# 2_ALARM.net
KiCad netlist of a schematic drawn in Altium Designer
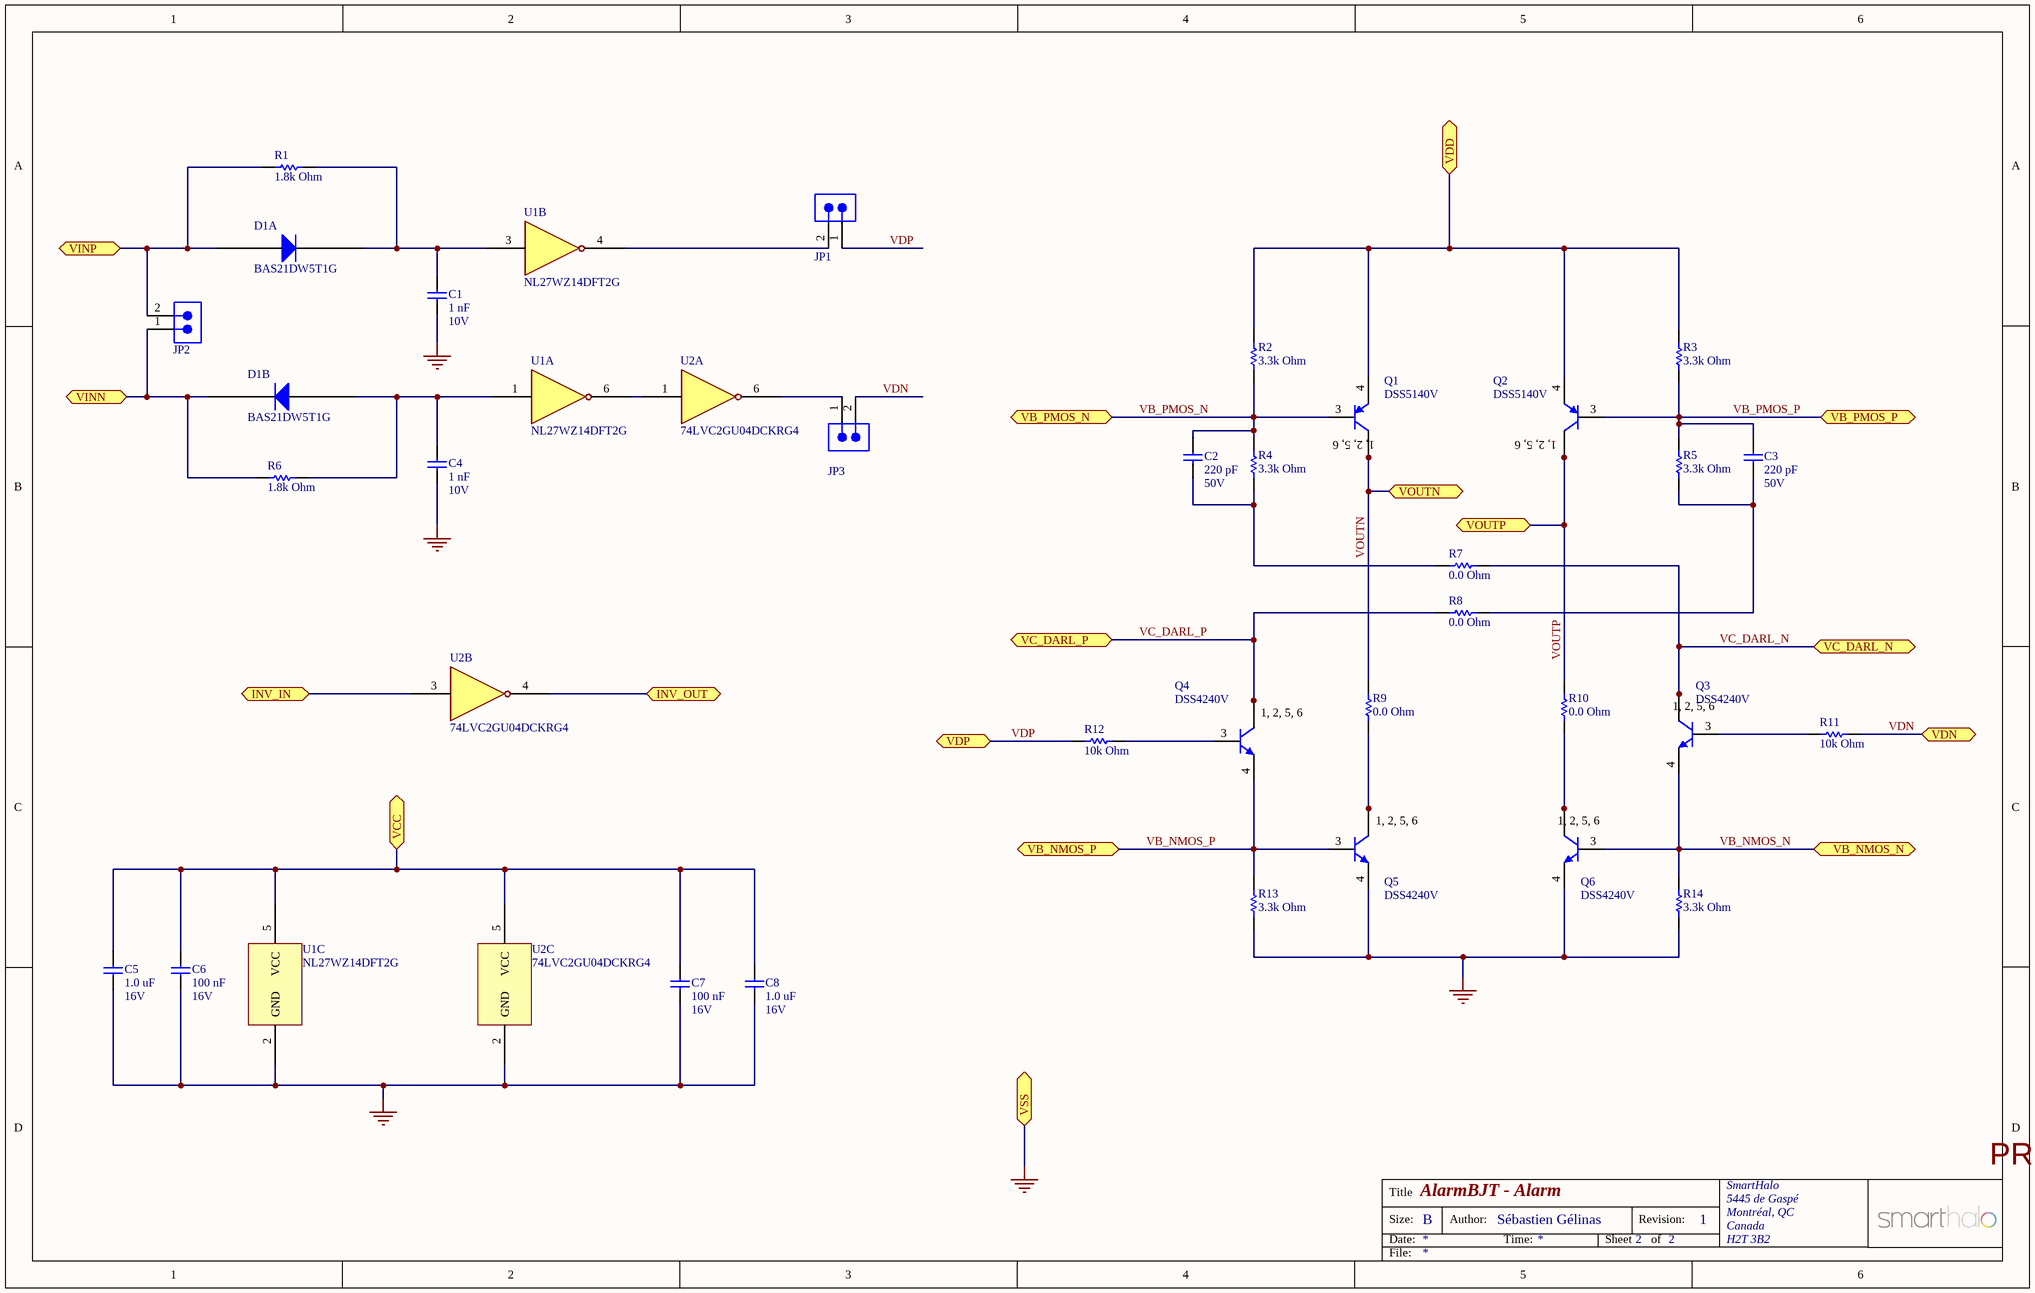
[diagram p0: 2_ALARM.SchDoc]

(export (version "E")
  (design (tool "Eeschema 10.0.6"))
  (components
    (comp (ref "C1")
      (value "1 nF")
      (footprint "Varitron_CAP0603")
      (description "1 nF 10V X7R 10% 0603 (1608 Metric)  SMD")
      (fields (field (name "TOLERANCE") "10%") (field (name "VOLTAGE RATING") "10V"))
      (libsource (lib "SmartHalo") (part "Varitron_CAP0603"))
    )
    (comp (ref "C2")
      (value "220 pF")
      (footprint "Varitron_CAP0603")
      (description "220 pF 50V X7R 10% 0603 (1608 Metric)  SMD")
      (fields (field (name "TOLERANCE") "10%") (field (name "VOLTAGE RATING") "50V"))
      (libsource (lib "SmartHalo") (part "Varitron_CAP0603"))
    )
    (comp (ref "C3")
      (value "220 pF")
      (footprint "Varitron_CAP0603")
      (description "220 pF 50V X7R 10% 0603 (1608 Metric)  SMD")
      (fields (field (name "TOLERANCE") "10%") (field (name "VOLTAGE RATING") "50V"))
      (libsource (lib "SmartHalo") (part "Varitron_CAP0603"))
    )
    (comp (ref "C4")
      (value "1 nF")
      (footprint "Varitron_CAP0603")
      (description "1 nF V TEMP TOL% 0603 (1608 Metric)  SMD")
      (fields (field (name "TOLERANCE") "10%") (field (name "VOLTAGE RATING") "10V"))
      (libsource (lib "SmartHalo") (part "Varitron_CAP0603"))
    )
    (comp (ref "C5")
      (value "1.0 uF")
      (footprint "Varitron_CAP0603")
      (description "1.0 uF 16V X7R 10% 0603 (1608 Metric)  SMD")
      (fields (field (name "TOLERANCE") "10%") (field (name "VOLTAGE RATING") "16V"))
      (libsource (lib "SmartHalo") (part "Varitron_CAP0603"))
    )
    (comp (ref "C6")
      (value "100 nF")
      (footprint "Varitron_CAP0603")
      (description "100 nF 16V X7R 10% 0603 (1608 Metric)  SMD")
      (fields (field (name "TOLERANCE") "5%") (field (name "VOLTAGE RATING") "16V"))
      (libsource (lib "SmartHalo") (part "Varitron_CAP0603"))
    )
    (comp (ref "C7")
      (value "100 nF")
      (footprint "Varitron_CAP0603")
      (description "100 nF 16V X7R 10% 0603 (1608 Metric)  SMD")
      (fields (field (name "TOLERANCE") "10%") (field (name "VOLTAGE RATING") "16V"))
      (libsource (lib "SmartHalo") (part "Varitron_CAP0603"))
    )
    (comp (ref "C8")
      (value "1.0 uF")
      (footprint "Varitron_CAP0603")
      (description "1.0 uF 16V X7R 10% 0603 (1608 Metric)  SMD")
      (fields (field (name "TOLERANCE") "10%") (field (name "VOLTAGE RATING") "16V"))
      (libsource (lib "SmartHalo") (part "Varitron_CAP0603"))
    )
    (comp (ref "D1")
      (value "BAS21DW5T1G")
      (footprint "SC70-5")
      (description "High Voltage Switching Diode")
      (fields (field (name "MANUFACTURER") "ON Semiconductor"))
      (libsource (lib "SmartHalo") (part "BAS21DW5T1G"))
    )
    (comp (ref "JP1")
      (value "JMP_2PINS_100MILS")
      (footprint "HDR_2X1_100MILS")
      (description "Jumper, 100 mils, 2 pins")
      (libsource (lib "SmartHalo") (part "JMP_2PINS_100MILS"))
    )
    (comp (ref "JP2")
      (value "JMP_2PINS_100MILS")
      (footprint "HDR_2X1_100MILS")
      (description "Jumper, 100 mils, 2 pins")
      (libsource (lib "SmartHalo") (part "JMP_2PINS_100MILS"))
    )
    (comp (ref "JP3")
      (value "JMP_2PINS_100MILS")
      (footprint "HDR_2X1_100MILS")
      (description "Jumper, 100 mils, 2 pins")
      (libsource (lib "SmartHalo") (part "JMP_2PINS_100MILS"))
    )
    (comp (ref "Q1")
      (value "DSS5140V")
      (footprint "SOT563")
      (description "PNP SMT Transistor, Low VCESAT")
      (fields (field (name "MANUFACTURER") "Diodes Inc."))
      (libsource (lib "SmartHalo") (part "DSS5140V"))
    )
    (comp (ref "Q2")
      (value "DSS5140V")
      (footprint "SOT563")
      (description "PNP SMT Transistor, Low VCESAT")
      (fields (field (name "MANUFACTURER") "Diodes Inc."))
      (libsource (lib "SmartHalo") (part "DSS5140V"))
    )
    (comp (ref "Q3")
      (value "DSS4240V")
      (footprint "SOT563")
      (description "NPN SMT Transistor, Low VCESAT")
      (fields (field (name "MANUFACTURER") "Diodes Inc."))
      (libsource (lib "SmartHalo") (part "DSS4240V"))
    )
    (comp (ref "Q4")
      (value "DSS4240V")
      (footprint "SOT563")
      (description "NPN SMT Transistor, Low VCESAT")
      (fields (field (name "MANUFACTURER") "Diodes Inc."))
      (libsource (lib "SmartHalo") (part "DSS4240V"))
    )
    (comp (ref "Q5")
      (value "DSS4240V")
      (footprint "SOT563")
      (description "NPN SMT Transistor, Low VCESAT")
      (fields (field (name "MANUFACTURER") "Diodes Inc."))
      (libsource (lib "SmartHalo") (part "DSS4240V"))
    )
    (comp (ref "Q6")
      (value "DSS4240V")
      (footprint "SOT563")
      (description "NPN SMT Transistor, Low VCESAT")
      (fields (field (name "MANUFACTURER") "Diodes Inc."))
      (libsource (lib "SmartHalo") (part "DSS4240V"))
    )
    (comp (ref "R1")
      (value "1.8k Ohm")
      (footprint "Varitron_RES0603")
      (description "1k8 0.063W 5%  0603 (1608 Metric)  SMD")
      (fields (field (name "TOLERANCE") "5%") (field (name "POWER") "0.063W"))
      (libsource (lib "SmartHalo") (part "Varitron_RES0603"))
    )
    (comp (ref "R2")
      (value "3.3k Ohm")
      (footprint "Varitron_RES0603")
      (description "3k3 0.063W 5%  0603 (1608 Metric)  SMD")
      (fields (field (name "TOLERANCE") "5%") (field (name "POWER") "0.063W"))
      (libsource (lib "SmartHalo") (part "Varitron_RES0603"))
    )
    (comp (ref "R3")
      (value "3.3k Ohm")
      (footprint "Varitron_RES0603")
      (description "3k3 0.063W 5%  0603 (1608 Metric)  SMD")
      (fields (field (name "TOLERANCE") "5%") (field (name "POWER") "0.063W"))
      (libsource (lib "SmartHalo") (part "Varitron_RES0603"))
    )
    (comp (ref "R4")
      (value "3.3k Ohm")
      (footprint "Varitron_RES0603")
      (description "3k3 0.063W 5%  0603 (1608 Metric)  SMD")
      (fields (field (name "TOLERANCE") "5%") (field (name "POWER") "0.063W"))
      (libsource (lib "SmartHalo") (part "Varitron_RES0603"))
    )
    (comp (ref "R5")
      (value "3.3k Ohm")
      (footprint "Varitron_RES0603")
      (description "3k3 0.063W 5%  0603 (1608 Metric)  SMD")
      (fields (field (name "TOLERANCE") "5%") (field (name "POWER") "0.063W"))
      (libsource (lib "SmartHalo") (part "Varitron_RES0603"))
    )
    (comp (ref "R6")
      (value "1.8k Ohm")
      (footprint "Varitron_RES0603")
      (description "1k8 0.063W 5%  0603 (1608 Metric)  SMD")
      (fields (field (name "TOLERANCE") "5%") (field (name "POWER") "0.063W"))
      (libsource (lib "SmartHalo") (part "Varitron_RES0603"))
    )
    (comp (ref "R7")
      (value "0.0 Ohm")
      (footprint "Varitron_RES0603")
      (description "0R0 0..1W JUMPER  0603 (1608 Metric)  SMD")
      (fields (field (name "TOLERANCE") "JUMPER") (field (name "POWER") "0.1W"))
      (libsource (lib "SmartHalo") (part "Varitron_RES0603"))
    )
    (comp (ref "R8")
      (value "0.0 Ohm")
      (footprint "Varitron_RES0603")
      (description "0R0 0..1W JUMPER  0603 (1608 Metric)  SMD")
      (fields (field (name "TOLERANCE") "JUMPER") (field (name "POWER") "0.1W"))
      (libsource (lib "SmartHalo") (part "Varitron_RES0603"))
    )
    (comp (ref "R9")
      (value "0.0 Ohm")
      (footprint "Varitron_RES0603")
      (description "0R0 0..1W JUMPER  0603 (1608 Metric)  SMD")
      (fields (field (name "TOLERANCE") "JUMPER") (field (name "POWER") "0.1W"))
      (libsource (lib "SmartHalo") (part "Varitron_RES0603"))
    )
    (comp (ref "R10")
      (value "0.0 Ohm")
      (footprint "Varitron_RES0603")
      (description "0R0 0..1W JUMPER  0603 (1608 Metric)  SMD")
      (fields (field (name "TOLERANCE") "JUMPER") (field (name "POWER") "0.1W"))
      (libsource (lib "SmartHalo") (part "Varitron_RES0603"))
    )
    (comp (ref "R11")
      (value "10k Ohm")
      (footprint "Varitron_RES0603")
      (description "10k 0.063W 5%  0603 (1608 Metric)  SMD")
      (fields (field (name "TOLERANCE") "5%") (field (name "POWER") "0.063W"))
      (libsource (lib "SmartHalo") (part "Varitron_RES0603"))
    )
    (comp (ref "R12")
      (value "10k Ohm")
      (footprint "Varitron_RES0603")
      (description "10k 0.063W 5%  0603 (1608 Metric)  SMD")
      (fields (field (name "TOLERANCE") "5%") (field (name "POWER") "0.063W"))
      (libsource (lib "SmartHalo") (part "Varitron_RES0603"))
    )
    (comp (ref "R13")
      (value "3.3k Ohm")
      (footprint "Varitron_RES0603")
      (description "3k3 0.063W 5%  0603 (1608 Metric)  SMD")
      (fields (field (name "TOLERANCE") "5%") (field (name "POWER") "0.063W"))
      (libsource (lib "SmartHalo") (part "Varitron_RES0603"))
    )
    (comp (ref "R14")
      (value "3.3k Ohm")
      (footprint "Varitron_RES0603")
      (description "3k3 0.063W 5%  0603 (1608 Metric)  SMD")
      (fields (field (name "TOLERANCE") "5%") (field (name "POWER") "0.063W"))
      (libsource (lib "SmartHalo") (part "Varitron_RES0603"))
    )
    (comp (ref "U1")
      (value "NL27WZ14DFT2G")
      (footprint "SOT363_SC70_6")
      (description "IC Dual Inverter with Schmitt Trigger Inputs")
      (fields (field (name "MANUFACTURER") "ON Semiconductor"))
      (libsource (lib "SmartHalo") (part "NL27WZ14DFT2G"))
    )
    (comp (ref "U2")
      (value "74LVC2GU04DCKRG4")
      (footprint "SOT363_SC70_6")
      (description "Dual Inverter Gate")
      (fields (field (name "MANUFACTURER") "Texas Instruments"))
      (libsource (lib "SmartHalo") (part "74LVC2GU04DCKRG4"))
    )
  )
  (nets
    (net (code "1") (name "/INV_IN") (class "Default")
      (node (ref "U2") (pin "3") (pinfunction "3_3") (pintype "passive"))
    )
    (net (code "2") (name "/INV_OUT") (class "Default")
      (node (ref "U2") (pin "4") (pinfunction "4_4") (pintype "passive"))
    )
    (net (code "3") (name "/VB_NMOS_N") (class "Default")
      (node (ref "Q3") (pin "4") (pinfunction "E_4") (pintype "passive"))
      (node (ref "Q6") (pin "3") (pinfunction "B_3") (pintype "passive"))
      (node (ref "R14") (pin "2") (pinfunction "2_2") (pintype "passive"))
    )
    (net (code "4") (name "/VB_NMOS_P") (class "Default")
      (node (ref "Q4") (pin "4") (pinfunction "E_4") (pintype "passive"))
      (node (ref "Q5") (pin "3") (pinfunction "B_3") (pintype "passive"))
      (node (ref "R13") (pin "1") (pinfunction "1_1") (pintype "passive"))
    )
    (net (code "5") (name "/VB_PMOS_N") (class "Default")
      (node (ref "C2") (pin "2") (pinfunction "2_2") (pintype "passive"))
      (node (ref "Q1") (pin "3") (pinfunction "B_3") (pintype "passive"))
      (node (ref "R2") (pin "1") (pinfunction "1_1") (pintype "passive"))
      (node (ref "R4") (pin "2") (pinfunction "2_2") (pintype "passive"))
    )
    (net (code "6") (name "/VB_PMOS_P") (class "Default")
      (node (ref "C3") (pin "2") (pinfunction "2_2") (pintype "passive"))
      (node (ref "Q2") (pin "3") (pinfunction "B_3") (pintype "passive"))
      (node (ref "R3") (pin "1") (pinfunction "1_1") (pintype "passive"))
      (node (ref "R5") (pin "2") (pinfunction "2_2") (pintype "passive"))
    )
    (net (code "7") (name "/VCC") (class "Default")
      (node (ref "C5") (pin "1") (pinfunction "1_1") (pintype "passive"))
      (node (ref "C6") (pin "1") (pinfunction "1_1") (pintype "passive"))
      (node (ref "C7") (pin "1") (pinfunction "1_1") (pintype "passive"))
      (node (ref "C8") (pin "1") (pinfunction "1_1") (pintype "passive"))
      (node (ref "U1") (pin "5") (pinfunction "VCC_5") (pintype "passive"))
      (node (ref "U2") (pin "5") (pinfunction "VCC_5") (pintype "passive"))
    )
    (net (code "8") (name "/VC_DARL_N") (class "Default")
      (node (ref "Q3") (pin "1") (pinfunction "C_1") (pintype "passive"))
      (node (ref "Q3") (pin "2") (pinfunction "C_2") (pintype "passive"))
      (node (ref "Q3") (pin "5") (pinfunction "C_5") (pintype "passive"))
      (node (ref "Q3") (pin "6") (pinfunction "C_6") (pintype "passive"))
      (node (ref "R7") (pin "1") (pinfunction "1_1") (pintype "passive"))
    )
    (net (code "9") (name "/VC_DARL_P") (class "Default")
      (node (ref "Q4") (pin "1") (pinfunction "C_1") (pintype "passive"))
      (node (ref "Q4") (pin "2") (pinfunction "C_2") (pintype "passive"))
      (node (ref "Q4") (pin "5") (pinfunction "C_5") (pintype "passive"))
      (node (ref "Q4") (pin "6") (pinfunction "C_6") (pintype "passive"))
      (node (ref "R8") (pin "2") (pinfunction "2_2") (pintype "passive"))
    )
    (net (code "10") (name "/VDD") (class "Default")
      (node (ref "Q1") (pin "4") (pinfunction "E_4") (pintype "passive"))
      (node (ref "Q2") (pin "4") (pinfunction "E_4") (pintype "passive"))
      (node (ref "R2") (pin "2") (pinfunction "2_2") (pintype "passive"))
      (node (ref "R3") (pin "2") (pinfunction "2_2") (pintype "passive"))
    )
    (net (code "11") (name "/VDN") (class "Default")
      (node (ref "JP3") (pin "2") (pinfunction "2_2") (pintype "passive"))
      (node (ref "R11") (pin "2") (pinfunction "2_2") (pintype "passive"))
    )
    (net (code "12") (name "/VDP") (class "Default")
      (node (ref "JP1") (pin "1") (pinfunction "1_1") (pintype "passive"))
      (node (ref "R12") (pin "2") (pinfunction "2_2") (pintype "passive"))
    )
    (net (code "13") (name "/VINN") (class "Default")
      (node (ref "D1") (pin "4") (pinfunction "Cathode_4") (pintype "passive"))
      (node (ref "JP2") (pin "1") (pinfunction "1_1") (pintype "passive"))
      (node (ref "R6") (pin "2") (pinfunction "2_2") (pintype "passive"))
    )
    (net (code "14") (name "/VINP") (class "Default")
      (node (ref "D1") (pin "1") (pinfunction "Anode_1") (pintype "passive"))
      (node (ref "JP2") (pin "2") (pinfunction "2_2") (pintype "passive"))
      (node (ref "R1") (pin "2") (pinfunction "2_2") (pintype "passive"))
    )
    (net (code "15") (name "/VOUTN") (class "Default")
      (node (ref "Q1") (pin "1") (pinfunction "C_1") (pintype "passive"))
      (node (ref "Q1") (pin "2") (pinfunction "C_2") (pintype "passive"))
      (node (ref "Q1") (pin "5") (pinfunction "C_5") (pintype "passive"))
      (node (ref "Q1") (pin "6") (pinfunction "C_6") (pintype "passive"))
      (node (ref "R9") (pin "1") (pinfunction "1_1") (pintype "passive"))
    )
    (net (code "16") (name "/VOUTP") (class "Default")
      (node (ref "Q2") (pin "1") (pinfunction "C_1") (pintype "passive"))
      (node (ref "Q2") (pin "2") (pinfunction "C_2") (pintype "passive"))
      (node (ref "Q2") (pin "5") (pinfunction "C_5") (pintype "passive"))
      (node (ref "Q2") (pin "6") (pinfunction "C_6") (pintype "passive"))
      (node (ref "R10") (pin "1") (pinfunction "1_1") (pintype "passive"))
    )
    (net (code "17") (name "GND") (class "Default")
      (node (ref "C1") (pin "1") (pinfunction "1_1") (pintype "passive"))
      (node (ref "C4") (pin "1") (pinfunction "1_1") (pintype "passive"))
      (node (ref "C5") (pin "2") (pinfunction "2_2") (pintype "passive"))
      (node (ref "C6") (pin "2") (pinfunction "2_2") (pintype "passive"))
      (node (ref "C7") (pin "2") (pinfunction "2_2") (pintype "passive"))
      (node (ref "C8") (pin "2") (pinfunction "2_2") (pintype "passive"))
      (node (ref "Q5") (pin "4") (pinfunction "E_4") (pintype "passive"))
      (node (ref "Q6") (pin "4") (pinfunction "E_4") (pintype "passive"))
      (node (ref "R13") (pin "2") (pinfunction "2_2") (pintype "passive"))
      (node (ref "R14") (pin "1") (pinfunction "1_1") (pintype "passive"))
      (node (ref "U1") (pin "2") (pinfunction "GND_2") (pintype "passive"))
      (node (ref "U2") (pin "2") (pinfunction "GND_2") (pintype "passive"))
    )
    (net (code "18") (name "Net-(C2-Pad1)") (class "Default")
      (node (ref "C2") (pin "1") (pinfunction "1_1") (pintype "passive"))
      (node (ref "R4") (pin "1") (pinfunction "1_1") (pintype "passive"))
      (node (ref "R7") (pin "2") (pinfunction "2_2") (pintype "passive"))
    )
    (net (code "19") (name "Net-(C3-Pad1)") (class "Default")
      (node (ref "C3") (pin "1") (pinfunction "1_1") (pintype "passive"))
      (node (ref "R5") (pin "1") (pinfunction "1_1") (pintype "passive"))
      (node (ref "R8") (pin "1") (pinfunction "1_1") (pintype "passive"))
    )
    (net (code "20") (name "Net-(D1A-Cathode)") (class "Default")
      (node (ref "C1") (pin "2") (pinfunction "2_2") (pintype "passive"))
      (node (ref "D1") (pin "5") (pinfunction "Cathode_5") (pintype "passive"))
      (node (ref "R1") (pin "1") (pinfunction "1_1") (pintype "passive"))
      (node (ref "U1") (pin "3") (pinfunction "3_3") (pintype "passive"))
    )
    (net (code "21") (name "Net-(D1B-Anode)") (class "Default")
      (node (ref "C4") (pin "2") (pinfunction "2_2") (pintype "passive"))
      (node (ref "D1") (pin "3") (pinfunction "Anode_3") (pintype "passive"))
      (node (ref "R6") (pin "1") (pinfunction "1_1") (pintype "passive"))
      (node (ref "U1") (pin "1") (pinfunction "1_1") (pintype "passive"))
    )
    (net (code "22") (name "Net-(JP1-Pad2)") (class "Default")
      (node (ref "JP1") (pin "2") (pinfunction "2_2") (pintype "passive"))
      (node (ref "U1") (pin "4") (pinfunction "4_4") (pintype "passive"))
    )
    (net (code "23") (name "Net-(JP3-Pad1)") (class "Default")
      (node (ref "JP3") (pin "1") (pinfunction "1_1") (pintype "passive"))
      (node (ref "U2") (pin "6") (pinfunction "6_6") (pintype "passive"))
    )
    (net (code "24") (name "Net-(Q3-B)") (class "Default")
      (node (ref "Q3") (pin "3") (pinfunction "B_3") (pintype "passive"))
      (node (ref "R11") (pin "1") (pinfunction "1_1") (pintype "passive"))
    )
    (net (code "25") (name "Net-(Q4-B)") (class "Default")
      (node (ref "Q4") (pin "3") (pinfunction "B_3") (pintype "passive"))
      (node (ref "R12") (pin "1") (pinfunction "1_1") (pintype "passive"))
    )
    (net (code "26") (name "Net-(Q5-C-Pad1)") (class "Default")
      (node (ref "Q5") (pin "1") (pinfunction "C_1") (pintype "passive"))
      (node (ref "Q5") (pin "2") (pinfunction "C_2") (pintype "passive"))
      (node (ref "Q5") (pin "5") (pinfunction "C_5") (pintype "passive"))
      (node (ref "Q5") (pin "6") (pinfunction "C_6") (pintype "passive"))
      (node (ref "R9") (pin "2") (pinfunction "2_2") (pintype "passive"))
    )
    (net (code "27") (name "Net-(Q6-C-Pad1)") (class "Default")
      (node (ref "Q6") (pin "1") (pinfunction "C_1") (pintype "passive"))
      (node (ref "Q6") (pin "2") (pinfunction "C_2") (pintype "passive"))
      (node (ref "Q6") (pin "5") (pinfunction "C_5") (pintype "passive"))
      (node (ref "Q6") (pin "6") (pinfunction "C_6") (pintype "passive"))
      (node (ref "R10") (pin "2") (pinfunction "2_2") (pintype "passive"))
    )
    (net (code "28") (name "Net-(U1-Pad6)") (class "Default")
      (node (ref "U1") (pin "6") (pinfunction "6_6") (pintype "passive"))
      (node (ref "U2") (pin "1") (pinfunction "1_1") (pintype "passive"))
    )
    (net (code "29") (name "unconnected-(D1-Pad2)") (class "Default")
      (node (ref "D1") (pin "2") (pinfunction "2_2") (pintype "passive"))
    )
  )
)
